# STC12_CH340E.net
KiCad netlist of a schematic drawn in Altium Designer
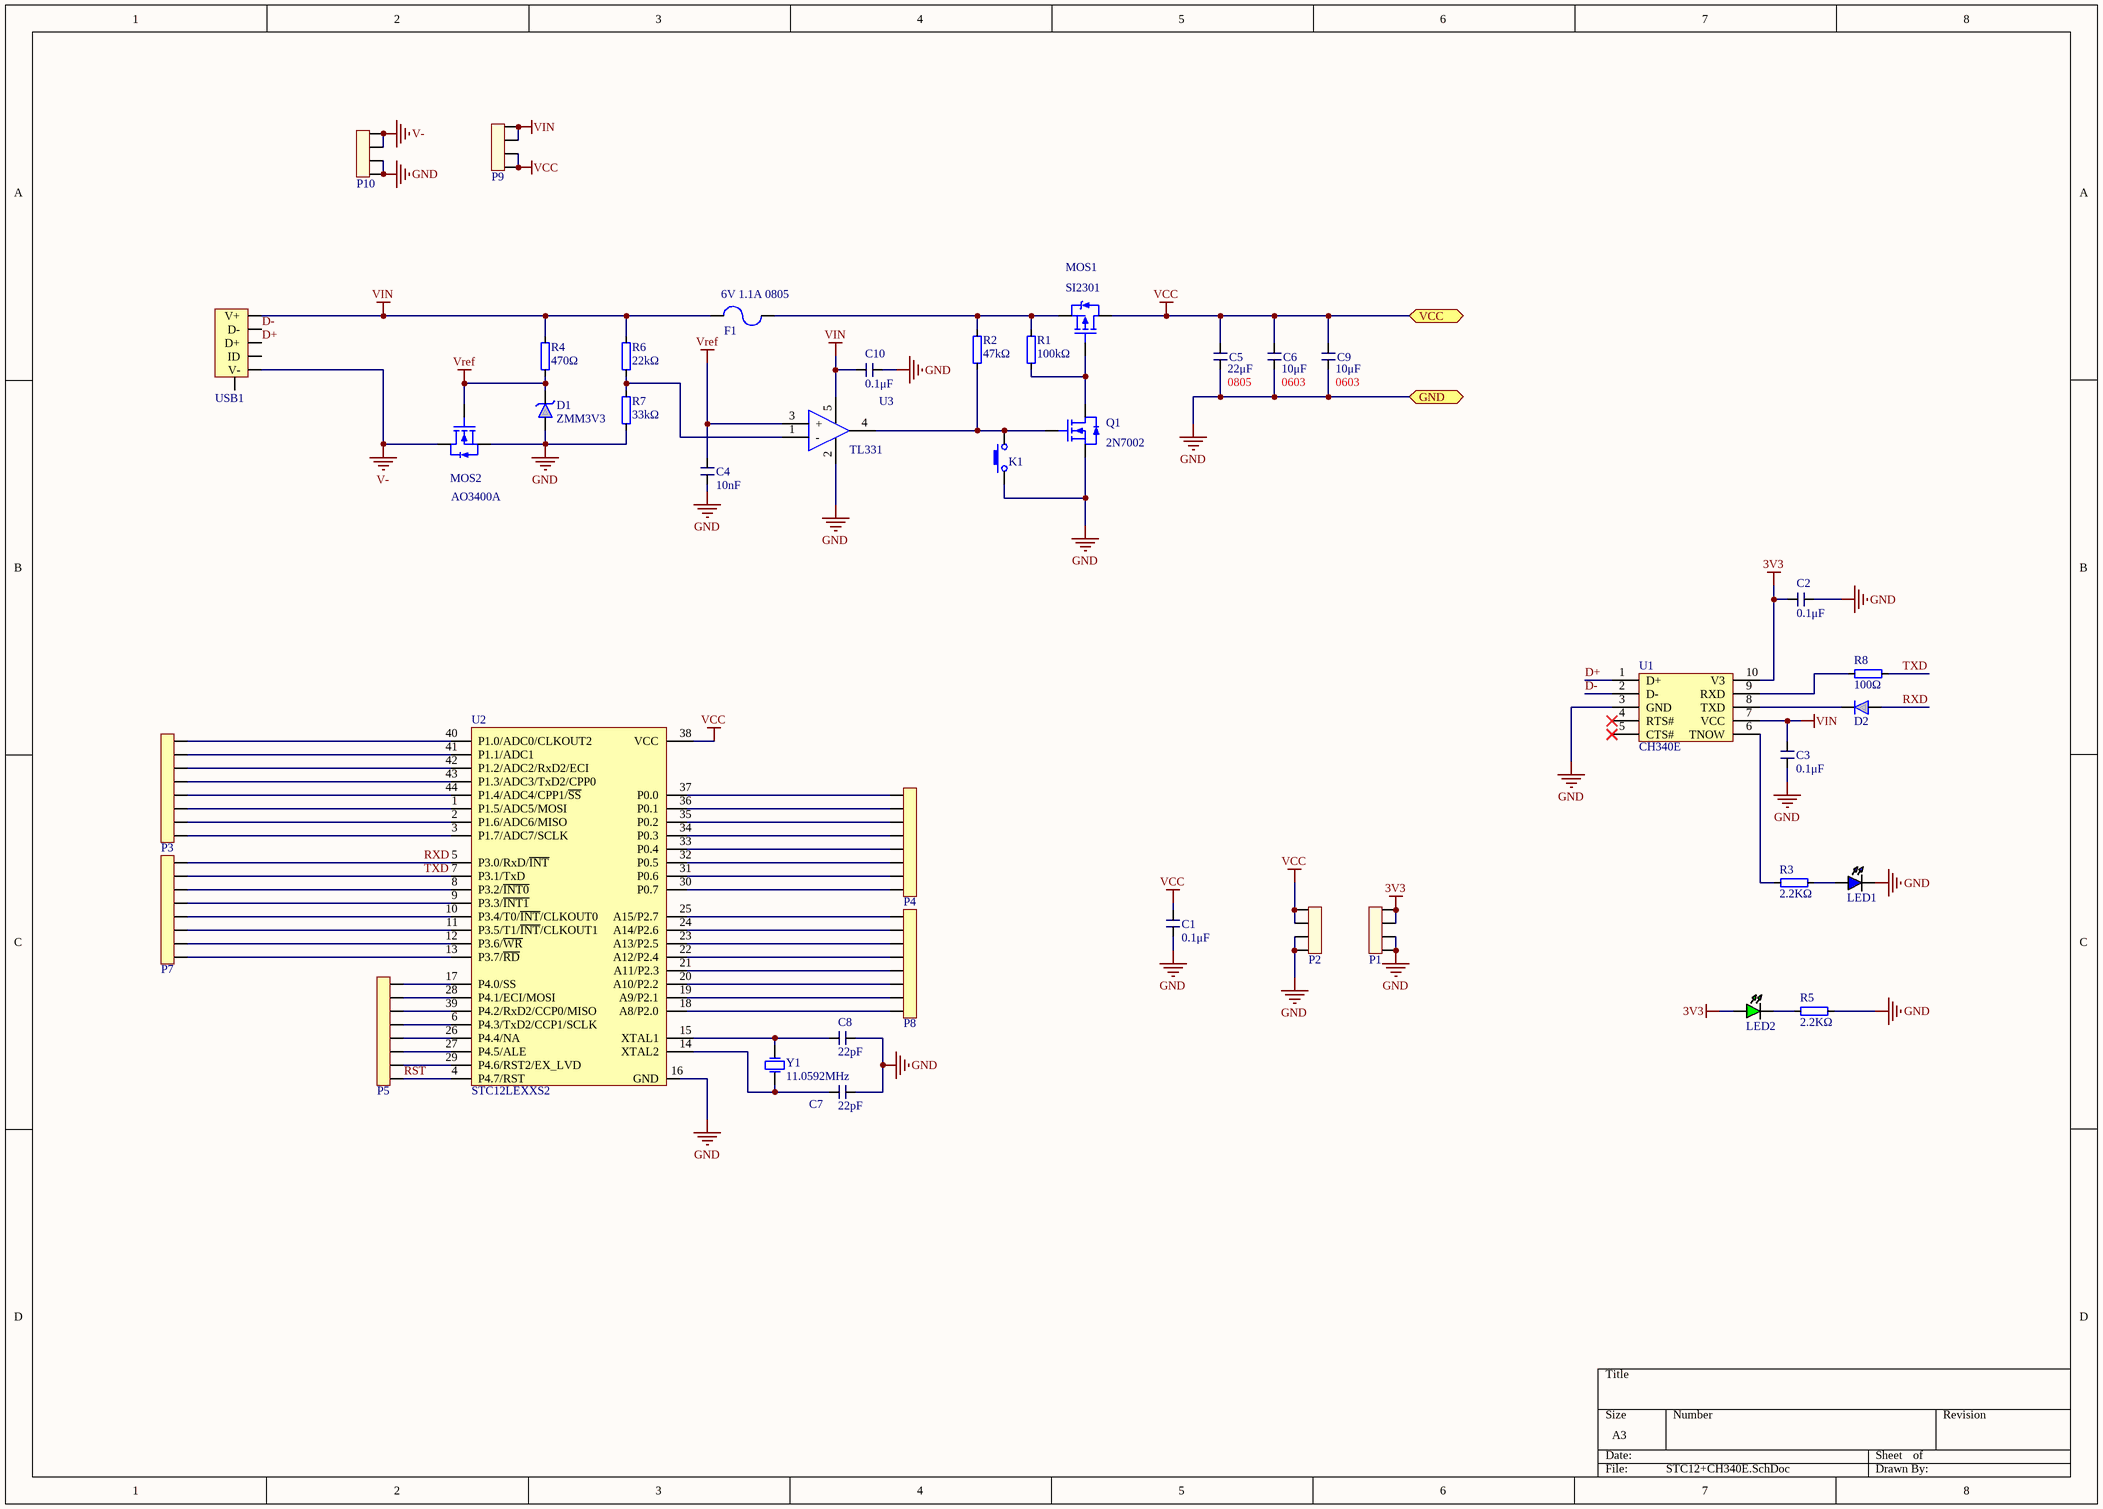
[diagram p0: STC12+CH340E.SchDoc]

(export (version "E")
  (design (tool "Eeschema 10.0.6"))
  (components
    (comp (ref "C1") (value "0.1μF") (footprint "C_0603") (libsource (lib "节能库") (part "C_0603")))
    (comp (ref "C2") (value "0.1μF") (footprint "C_0603") (libsource (lib "节能库") (part "C_0603")))
    (comp (ref "C3") (value "0.1μF") (footprint "C_0603") (libsource (lib "节能库") (part "C_0603")))
    (comp (ref "C4") (value "10nF") (footprint "C_0603") (libsource (lib "节能库") (part "C_0603")))
    (comp (ref "C5") (value "22μF") (footprint "C_0805") (libsource (lib "节能库") (part "C_0805")))
    (comp (ref "C6") (value "10μF") (footprint "C_0603") (libsource (lib "节能库") (part "C_0603")))
    (comp (ref "C7") (value "22pF") (footprint "C_0603") (libsource (lib "节能库") (part "C_0603")))
    (comp (ref "C8") (value "22pF") (footprint "C_0603") (libsource (lib "节能库") (part "C_0603")))
    (comp (ref "C9") (value "10μF") (footprint "C_0603") (libsource (lib "节能库") (part "C_0603")))
    (comp (ref "C10") (value "0.1μF") (footprint "C_0603") (libsource (lib "节能库") (part "C_0603")))
    (comp (ref "D1") (value "ZMM3V3") (footprint "SOD_80") (libsource (lib "节能库") (part "ZMMxxV")))
    (comp (ref "D2") (value "1N4148WS") (footprint "SOD_323") (libsource (lib "节能库") (part "1N4148WS")))
    (comp (ref "F1") (value "6V 1.1A 0805") (footprint "FB_0805") (libsource (lib "节能库") (part "FUSE_0805")))
    (comp (ref "K1")
      (value "TACT SWITCH_2_SMD")
      (footprint "TACT SWITCH_2_SMD")
      (libsource (lib "节能库") (part "TACT SWITCH_2_SMD"))
    )
    (comp (ref "LED1")
      (value "LED_0603-B")
      (footprint "LED_0603-B")
      (libsource (lib "节能库") (part "LED_0603-B"))
    )
    (comp (ref "LED2")
      (value "LED_0603-G")
      (footprint "LED_0603-G")
      (libsource (lib "节能库") (part "LED_0603-G"))
    )
    (comp (ref "MOS1") (value "SI2301") (footprint "SOT_23_3") (libsource (lib "节能库") (part "SI2301")))
    (comp (ref "MOS2") (value "AO3400A") (footprint "SOT_23_3") (libsource (lib "节能库") (part "AO3400A")))
    (comp (ref "P1") (value "PIN4") (footprint "PIN_4") (libsource (lib "节能库") (part "PIN4")))
    (comp (ref "P2") (value "PIN4") (footprint "PIN_4") (libsource (lib "") (part "PIN4_1")))
    (comp (ref "P3") (value "PIN8") (footprint "PIN_8") (libsource (lib "节能库") (part "PIN8")))
    (comp (ref "P4") (value "PIN8") (footprint "PIN_8") (libsource (lib "") (part "PIN8_1")))
    (comp (ref "P5") (value "PIN8") (footprint "PIN_8") (libsource (lib "节能库") (part "PIN8")))
    (comp (ref "P7") (value "PIN8") (footprint "PIN_8") (libsource (lib "节能库") (part "PIN8")))
    (comp (ref "P8") (value "PIN8") (footprint "PIN_8") (libsource (lib "") (part "PIN8_1")))
    (comp (ref "P9") (value "PIN4") (footprint "PIN_4") (libsource (lib "") (part "PIN4_2")))
    (comp (ref "P10") (value "PIN4") (footprint "PIN_4") (libsource (lib "") (part "PIN4_2")))
    (comp (ref "Q1") (value "2N7002") (footprint "SOT_23_3") (libsource (lib "节能库") (part "2N7002")))
    (comp (ref "R1") (value "100kΩ") (footprint "R_0603") (libsource (lib "节能库") (part "R_0603")))
    (comp (ref "R2") (value "47kΩ") (footprint "R_0603") (libsource (lib "节能库") (part "R_0603")))
    (comp (ref "R3") (value "2.2KΩ") (footprint "R_0603") (libsource (lib "节能库") (part "R_0603")))
    (comp (ref "R4") (value "470Ω") (footprint "R_0603") (libsource (lib "节能库") (part "R_0603")))
    (comp (ref "R5") (value "2.2KΩ") (footprint "R_0603") (libsource (lib "节能库") (part "R_0603")))
    (comp (ref "R6") (value "22kΩ") (footprint "R_0603") (libsource (lib "节能库") (part "R_0603")))
    (comp (ref "R7") (value "33kΩ") (footprint "R_0603") (libsource (lib "节能库") (part "R_0603")))
    (comp (ref "R8") (value "100Ω") (footprint "R_0603") (libsource (lib "节能库") (part "R_0603")))
    (comp (ref "U1") (value "CH340E") (footprint "MSOP_10") (libsource (lib "节能库") (part "CH340E")))
    (comp (ref "U2")
      (value "STC12LEXXS2")
      (footprint "LQFP_44")
      (libsource (lib "节能库") (part "STC12LE5AXXS2 - LQPF44"))
    )
    (comp (ref "U3") (value "TL331") (footprint "SOT_23_5") (libsource (lib "节能库") (part "TL331")))
    (comp (ref "USB1")
      (value "MICRO USB B")
      (footprint "MICRO USB B")
      (libsource (lib "节能库") (part "MICRO USB B"))
    )
    (comp (ref "Y1")
      (value "11.0592MHz")
      (footprint "Crystal_HC_49US")
      (libsource (lib "节能库") (part "Crystal_HC_49US"))
    )
  )
  (nets
    (net (code "1") (name "/D+") (class "Default")
      (node (ref "U1") (pin "1") (pinfunction "D+_1") (pintype "passive"))
      (node (ref "USB1") (pin "3") (pinfunction "D+_3") (pintype "passive"))
    )
    (net (code "2") (name "/D-") (class "Default")
      (node (ref "U1") (pin "2") (pinfunction "D-_2") (pintype "passive"))
      (node (ref "USB1") (pin "2") (pinfunction "D-_2") (pintype "passive"))
    )
    (net (code "3") (name "/RST") (class "Default")
      (node (ref "P5") (pin "8") (pinfunction "8_8") (pintype "passive"))
      (node (ref "U2") (pin "4") (pinfunction "P4.7/RST_4") (pintype "passive"))
    )
    (net (code "4") (name "/RXD") (class "Default")
      (node (ref "D2") (pin "1") (pinfunction "A_1") (pintype "passive"))
      (node (ref "P7") (pin "1") (pinfunction "1_1") (pintype "passive"))
      (node (ref "U2") (pin "5") (pinfunction "P3.0/RxD/~{INT}_5") (pintype "passive"))
    )
    (net (code "5") (name "/TXD") (class "Default")
      (node (ref "P7") (pin "2") (pinfunction "2_2") (pintype "passive"))
      (node (ref "R8") (pin "2") (pintype "passive"))
      (node (ref "U2") (pin "7") (pinfunction "P3.1/TxD_7") (pintype "passive"))
    )
    (net (code "6") (name "3V3") (class "Default")
      (node (ref "C2") (pin "2") (pinfunction "2_2") (pintype "passive"))
      (node (ref "LED2") (pin "1") (pinfunction "1_1") (pintype "passive"))
      (node (ref "P1") (pin "3") (pinfunction "3_3") (pintype "passive"))
      (node (ref "P1") (pin "4") (pinfunction "4_4") (pintype "passive"))
      (node (ref "U1") (pin "10") (pinfunction "V3_10") (pintype "passive"))
    )
    (net (code "7") (name "GND") (class "Default")
      (node (ref "C1") (pin "2") (pinfunction "2_2") (pintype "passive"))
      (node (ref "C10") (pin "2") (pinfunction "2_2") (pintype "passive"))
      (node (ref "C2") (pin "1") (pinfunction "1_1") (pintype "passive"))
      (node (ref "C3") (pin "1") (pinfunction "1_1") (pintype "passive"))
      (node (ref "C4") (pin "2") (pinfunction "2_2") (pintype "passive"))
      (node (ref "C5") (pin "2") (pinfunction "2_2") (pintype "passive"))
      (node (ref "C6") (pin "2") (pinfunction "2_2") (pintype "passive"))
      (node (ref "C7") (pin "2") (pinfunction "2_2") (pintype "passive"))
      (node (ref "C8") (pin "2") (pinfunction "2_2") (pintype "passive"))
      (node (ref "C9") (pin "2") (pinfunction "2_2") (pintype "passive"))
      (node (ref "D1") (pin "1") (pinfunction "A_1") (pintype "passive"))
      (node (ref "K1") (pin "1") (pinfunction "1_1") (pintype "passive"))
      (node (ref "LED1") (pin "2") (pinfunction "2_2") (pintype "passive"))
      (node (ref "MOS2") (pin "2") (pinfunction "S_2") (pintype "passive"))
      (node (ref "P1") (pin "1") (pinfunction "1_1") (pintype "passive"))
      (node (ref "P1") (pin "2") (pinfunction "2_2") (pintype "passive"))
      (node (ref "P10") (pin "3") (pinfunction "3_3") (pintype "passive"))
      (node (ref "P10") (pin "4") (pinfunction "4_4") (pintype "passive"))
      (node (ref "P2") (pin "1") (pinfunction "1_1") (pintype "passive"))
      (node (ref "P2") (pin "2") (pinfunction "2_2") (pintype "passive"))
      (node (ref "Q1") (pin "2") (pinfunction "S_2") (pintype "passive"))
      (node (ref "R5") (pin "2") (pintype "passive"))
      (node (ref "R7") (pin "1") (pintype "passive"))
      (node (ref "U1") (pin "3") (pinfunction "GND_3") (pintype "passive"))
      (node (ref "U2") (pin "16") (pinfunction "GND_16") (pintype "passive"))
      (node (ref "U3") (pin "2") (pinfunction "GND_2") (pintype "passive"))
    )
    (net (code "8") (name "Net-(D2-K)") (class "Default")
      (node (ref "D2") (pin "2") (pinfunction "K_2") (pintype "passive"))
      (node (ref "U1") (pin "8") (pinfunction "TXD_8") (pintype "passive"))
    )
    (net (code "9") (name "Net-(LED1-Pad1)") (class "Default")
      (node (ref "LED1") (pin "1") (pinfunction "1_1") (pintype "passive"))
      (node (ref "R3") (pin "2") (pintype "passive"))
    )
    (net (code "10") (name "Net-(LED2-Pad2)") (class "Default")
      (node (ref "LED2") (pin "2") (pinfunction "2_2") (pintype "passive"))
      (node (ref "R5") (pin "1") (pintype "passive"))
    )
    (net (code "11") (name "Net-(MOS1-G)") (class "Default")
      (node (ref "MOS1") (pin "1") (pinfunction "G_1") (pintype "passive"))
      (node (ref "Q1") (pin "3") (pinfunction "D_3") (pintype "passive"))
      (node (ref "R1") (pin "1") (pintype "passive"))
    )
    (net (code "12") (name "Net-(MOS1-S)") (class "Default")
      (node (ref "F1") (pin "2") (pinfunction "2_2") (pintype "passive"))
      (node (ref "MOS1") (pin "2") (pinfunction "S_2") (pintype "passive"))
      (node (ref "R1") (pin "2") (pintype "passive"))
      (node (ref "R2") (pin "2") (pintype "passive"))
    )
    (net (code "13") (name "Net-(Q1-G)") (class "Default")
      (node (ref "K1") (pin "2") (pinfunction "2_2") (pintype "passive"))
      (node (ref "Q1") (pin "1") (pinfunction "G_1") (pintype "passive"))
      (node (ref "R2") (pin "1") (pintype "passive"))
      (node (ref "U3") (pin "4") (pinfunction "OUT_4") (pintype "passive"))
    )
    (net (code "14") (name "Net-(U1-RXD)") (class "Default")
      (node (ref "R8") (pin "1") (pintype "passive"))
      (node (ref "U1") (pin "9") (pinfunction "RXD_9") (pintype "passive"))
    )
    (net (code "15") (name "Net-(U1-TNOW)") (class "Default")
      (node (ref "R3") (pin "1") (pintype "passive"))
      (node (ref "U1") (pin "6") (pinfunction "TNOW_6") (pintype "passive"))
    )
    (net (code "16") (name "Net-(U2-A8{slash}P2.0)") (class "Default")
      (node (ref "P8") (pin "1") (pinfunction "1_1") (pintype "passive"))
      (node (ref "U2") (pin "18") (pinfunction "A8/P2.0_18") (pintype "passive"))
    )
    (net (code "17") (name "Net-(U2-A9{slash}P2.1)") (class "Default")
      (node (ref "P8") (pin "2") (pinfunction "2_2") (pintype "passive"))
      (node (ref "U2") (pin "19") (pinfunction "A9/P2.1_19") (pintype "passive"))
    )
    (net (code "18") (name "Net-(U2-A10{slash}P2.2)") (class "Default")
      (node (ref "P8") (pin "3") (pinfunction "3_3") (pintype "passive"))
      (node (ref "U2") (pin "20") (pinfunction "A10/P2.2_20") (pintype "passive"))
    )
    (net (code "19") (name "Net-(U2-A11{slash}P2.3)") (class "Default")
      (node (ref "P8") (pin "4") (pinfunction "4_4") (pintype "passive"))
      (node (ref "U2") (pin "21") (pinfunction "A11/P2.3_21") (pintype "passive"))
    )
    (net (code "20") (name "Net-(U2-A12{slash}P2.4)") (class "Default")
      (node (ref "P8") (pin "5") (pinfunction "5_5") (pintype "passive"))
      (node (ref "U2") (pin "22") (pinfunction "A12/P2.4_22") (pintype "passive"))
    )
    (net (code "21") (name "Net-(U2-A13{slash}P2.5)") (class "Default")
      (node (ref "P8") (pin "6") (pinfunction "6_6") (pintype "passive"))
      (node (ref "U2") (pin "23") (pinfunction "A13/P2.5_23") (pintype "passive"))
    )
    (net (code "22") (name "Net-(U2-A14{slash}P2.6)") (class "Default")
      (node (ref "P8") (pin "7") (pinfunction "7_7") (pintype "passive"))
      (node (ref "U2") (pin "24") (pinfunction "A14/P2.6_24") (pintype "passive"))
    )
    (net (code "23") (name "Net-(U2-A15{slash}P2.7)") (class "Default")
      (node (ref "P8") (pin "8") (pinfunction "8_8") (pintype "passive"))
      (node (ref "U2") (pin "25") (pinfunction "A15/P2.7_25") (pintype "passive"))
    )
    (net (code "24") (name "Net-(U2-P0.0)") (class "Default")
      (node (ref "P4") (pin "8") (pinfunction "8_8") (pintype "passive"))
      (node (ref "U2") (pin "37") (pinfunction "P0.0_37") (pintype "passive"))
    )
    (net (code "25") (name "Net-(U2-P0.1)") (class "Default")
      (node (ref "P4") (pin "7") (pinfunction "7_7") (pintype "passive"))
      (node (ref "U2") (pin "36") (pinfunction "P0.1_36") (pintype "passive"))
    )
    (net (code "26") (name "Net-(U2-P0.2)") (class "Default")
      (node (ref "P4") (pin "6") (pinfunction "6_6") (pintype "passive"))
      (node (ref "U2") (pin "35") (pinfunction "P0.2_35") (pintype "passive"))
    )
    (net (code "27") (name "Net-(U2-P0.3)") (class "Default")
      (node (ref "P4") (pin "5") (pinfunction "5_5") (pintype "passive"))
      (node (ref "U2") (pin "34") (pinfunction "P0.3_34") (pintype "passive"))
    )
    (net (code "28") (name "Net-(U2-P0.4)") (class "Default")
      (node (ref "P4") (pin "4") (pinfunction "4_4") (pintype "passive"))
      (node (ref "U2") (pin "33") (pinfunction "P0.4_33") (pintype "passive"))
    )
    (net (code "29") (name "Net-(U2-P0.5)") (class "Default")
      (node (ref "P4") (pin "3") (pinfunction "3_3") (pintype "passive"))
      (node (ref "U2") (pin "32") (pinfunction "P0.5_32") (pintype "passive"))
    )
    (net (code "30") (name "Net-(U2-P0.6)") (class "Default")
      (node (ref "P4") (pin "2") (pinfunction "2_2") (pintype "passive"))
      (node (ref "U2") (pin "31") (pinfunction "P0.6_31") (pintype "passive"))
    )
    (net (code "31") (name "Net-(U2-P0.7)") (class "Default")
      (node (ref "P4") (pin "1") (pinfunction "1_1") (pintype "passive"))
      (node (ref "U2") (pin "30") (pinfunction "P0.7_30") (pintype "passive"))
    )
    (net (code "32") (name "Net-(U2-P1.0{slash}ADC0{slash}CLKOUT2)") (class "Default")
      (node (ref "P3") (pin "1") (pinfunction "1_1") (pintype "passive"))
      (node (ref "U2") (pin "40") (pinfunction "P1.0/ADC0/CLKOUT2_40") (pintype "passive"))
    )
    (net (code "33") (name "Net-(U2-P1.1{slash}ADC1)") (class "Default")
      (node (ref "P3") (pin "2") (pinfunction "2_2") (pintype "passive"))
      (node (ref "U2") (pin "41") (pinfunction "P1.1/ADC1_41") (pintype "passive"))
    )
    (net (code "34") (name "Net-(U2-P1.2{slash}ADC2{slash}RxD2{slash}ECI)") (class "Default")
      (node (ref "P3") (pin "3") (pinfunction "3_3") (pintype "passive"))
      (node (ref "U2") (pin "42") (pinfunction "P1.2/ADC2/RxD2/ECI_42") (pintype "passive"))
    )
    (net (code "35") (name "Net-(U2-P1.3{slash}ADC3{slash}TxD2{slash}CPP0)") (class "Default")
      (node (ref "P3") (pin "4") (pinfunction "4_4") (pintype "passive"))
      (node (ref "U2") (pin "43") (pinfunction "P1.3/ADC3/TxD2/CPP0_43") (pintype "passive"))
    )
    (net (code "36") (name "Net-(U2-P1.4{slash}ADC4{slash}CPP1{slash}~{SS})") (class "Default")
      (node (ref "P3") (pin "5") (pinfunction "5_5") (pintype "passive"))
      (node (ref "U2") (pin "44") (pinfunction "P1.4/ADC4/CPP1/~{SS}_44") (pintype "passive"))
    )
    (net (code "37") (name "Net-(U2-P1.5{slash}ADC5{slash}MOSI)") (class "Default")
      (node (ref "P3") (pin "6") (pinfunction "6_6") (pintype "passive"))
      (node (ref "U2") (pin "1") (pinfunction "P1.5/ADC5/MOSI_1") (pintype "passive"))
    )
    (net (code "38") (name "Net-(U2-P1.6{slash}ADC6{slash}MISO)") (class "Default")
      (node (ref "P3") (pin "7") (pinfunction "7_7") (pintype "passive"))
      (node (ref "U2") (pin "2") (pinfunction "P1.6/ADC6/MISO_2") (pintype "passive"))
    )
    (net (code "39") (name "Net-(U2-P1.7{slash}ADC7{slash}SCLK)") (class "Default")
      (node (ref "P3") (pin "8") (pinfunction "8_8") (pintype "passive"))
      (node (ref "U2") (pin "3") (pinfunction "P1.7/ADC7/SCLK_3") (pintype "passive"))
    )
    (net (code "40") (name "Net-(U2-P3.2{slash}~{INT0})") (class "Default")
      (node (ref "P7") (pin "3") (pinfunction "3_3") (pintype "passive"))
      (node (ref "U2") (pin "8") (pinfunction "P3.2/~{INT0}_8") (pintype "passive"))
    )
    (net (code "41") (name "Net-(U2-P3.3{slash}~{INT1})") (class "Default")
      (node (ref "P7") (pin "4") (pinfunction "4_4") (pintype "passive"))
      (node (ref "U2") (pin "9") (pinfunction "P3.3/~{INT1}_9") (pintype "passive"))
    )
    (net (code "42") (name "Net-(U2-P3.4{slash}T0{slash}~{INT}{slash}CLKOUT0)") (class "Default")
      (node (ref "P7") (pin "5") (pinfunction "5_5") (pintype "passive"))
      (node (ref "U2") (pin "10") (pinfunction "P3.4/T0/~{INT}/CLKOUT0_10") (pintype "passive"))
    )
    (net (code "43") (name "Net-(U2-P3.5{slash}T1{slash}~{INT}{slash}CLKOUT1)") (class "Default")
      (node (ref "P7") (pin "6") (pinfunction "6_6") (pintype "passive"))
      (node (ref "U2") (pin "11") (pinfunction "P3.5/T1/~{INT}/CLKOUT1_11") (pintype "passive"))
    )
    (net (code "44") (name "Net-(U2-P3.6{slash}~{WR})") (class "Default")
      (node (ref "P7") (pin "7") (pinfunction "7_7") (pintype "passive"))
      (node (ref "U2") (pin "12") (pinfunction "P3.6/~{WR}_12") (pintype "passive"))
    )
    (net (code "45") (name "Net-(U2-P3.7{slash}~{RD})") (class "Default")
      (node (ref "P7") (pin "8") (pinfunction "8_8") (pintype "passive"))
      (node (ref "U2") (pin "13") (pinfunction "P3.7/~{RD}_13") (pintype "passive"))
    )
    (net (code "46") (name "Net-(U2-P4.0{slash}SS)") (class "Default")
      (node (ref "P5") (pin "1") (pinfunction "1_1") (pintype "passive"))
      (node (ref "U2") (pin "17") (pinfunction "P4.0/SS_17") (pintype "passive"))
    )
    (net (code "47") (name "Net-(U2-P4.1{slash}ECI{slash}MOSI)") (class "Default")
      (node (ref "P5") (pin "2") (pinfunction "2_2") (pintype "passive"))
      (node (ref "U2") (pin "28") (pinfunction "P4.1/ECI/MOSI_28") (pintype "passive"))
    )
    (net (code "48") (name "Net-(U2-P4.2{slash}RxD2{slash}CCP0{slash}MISO)") (class "Default")
      (node (ref "P5") (pin "3") (pinfunction "3_3") (pintype "passive"))
      (node (ref "U2") (pin "39") (pinfunction "P4.2/RxD2/CCP0/MISO_39") (pintype "passive"))
    )
    (net (code "49") (name "Net-(U2-P4.3{slash}TxD2{slash}CCP1{slash}SCLK)") (class "Default")
      (node (ref "P5") (pin "4") (pinfunction "4_4") (pintype "passive"))
      (node (ref "U2") (pin "6") (pinfunction "P4.3/TxD2/CCP1/SCLK_6") (pintype "passive"))
    )
    (net (code "50") (name "Net-(U2-P4.4{slash}NA)") (class "Default")
      (node (ref "P5") (pin "5") (pinfunction "5_5") (pintype "passive"))
      (node (ref "U2") (pin "26") (pinfunction "P4.4/NA_26") (pintype "passive"))
    )
    (net (code "51") (name "Net-(U2-P4.5{slash}ALE)") (class "Default")
      (node (ref "P5") (pin "6") (pinfunction "6_6") (pintype "passive"))
      (node (ref "U2") (pin "27") (pinfunction "P4.5/ALE_27") (pintype "passive"))
    )
    (net (code "52") (name "Net-(U2-P4.6{slash}RST2{slash}EX_LVD)") (class "Default")
      (node (ref "P5") (pin "7") (pinfunction "7_7") (pintype "passive"))
      (node (ref "U2") (pin "29") (pinfunction "P4.6/RST2/EX_LVD_29") (pintype "passive"))
    )
    (net (code "53") (name "Net-(U2-XTAL1)") (class "Default")
      (node (ref "C8") (pin "1") (pinfunction "1_1") (pintype "passive"))
      (node (ref "U2") (pin "15") (pinfunction "XTAL1_15") (pintype "passive"))
      (node (ref "Y1") (pin "2") (pinfunction "OSC2_2") (pintype "passive"))
    )
    (net (code "54") (name "Net-(U2-XTAL2)") (class "Default")
      (node (ref "C7") (pin "1") (pinfunction "1_1") (pintype "passive"))
      (node (ref "U2") (pin "14") (pinfunction "XTAL2_14") (pintype "passive"))
      (node (ref "Y1") (pin "1") (pinfunction "OSC1_1") (pintype "passive"))
    )
    (net (code "55") (name "Net-(U3--)") (class "Default")
      (node (ref "R6") (pin "1") (pintype "passive"))
      (node (ref "R7") (pin "2") (pintype "passive"))
      (node (ref "U3") (pin "1") (pinfunction "-_1") (pintype "passive"))
    )
    (net (code "56") (name "V-") (class "Default")
      (node (ref "MOS2") (pin "3") (pinfunction "D_3") (pintype "passive"))
      (node (ref "P10") (pin "1") (pinfunction "1_1") (pintype "passive"))
      (node (ref "P10") (pin "2") (pinfunction "2_2") (pintype "passive"))
      (node (ref "USB1") (pin "5") (pinfunction "V-_5") (pintype "passive"))
    )
    (net (code "57") (name "VCC") (class "Default")
      (node (ref "C1") (pin "1") (pinfunction "1_1") (pintype "passive"))
      (node (ref "C5") (pin "1") (pinfunction "1_1") (pintype "passive"))
      (node (ref "C6") (pin "1") (pinfunction "1_1") (pintype "passive"))
      (node (ref "C9") (pin "1") (pinfunction "1_1") (pintype "passive"))
      (node (ref "MOS1") (pin "3") (pinfunction "D_3") (pintype "passive"))
      (node (ref "P2") (pin "3") (pinfunction "3_3") (pintype "passive"))
      (node (ref "P2") (pin "4") (pinfunction "4_4") (pintype "passive"))
      (node (ref "P9") (pin "3") (pinfunction "3_3") (pintype "passive"))
      (node (ref "P9") (pin "4") (pinfunction "4_4") (pintype "passive"))
      (node (ref "U2") (pin "38") (pinfunction "VCC_38") (pintype "passive"))
    )
    (net (code "58") (name "VIN") (class "Default")
      (node (ref "C10") (pin "1") (pinfunction "1_1") (pintype "passive"))
      (node (ref "C3") (pin "2") (pinfunction "2_2") (pintype "passive"))
      (node (ref "F1") (pin "1") (pinfunction "1_1") (pintype "passive"))
      (node (ref "P9") (pin "1") (pinfunction "1_1") (pintype "passive"))
      (node (ref "P9") (pin "2") (pinfunction "2_2") (pintype "passive"))
      (node (ref "R4") (pin "2") (pintype "passive"))
      (node (ref "R6") (pin "2") (pintype "passive"))
      (node (ref "U1") (pin "7") (pinfunction "VCC_7") (pintype "passive"))
      (node (ref "U3") (pin "5") (pinfunction "VCC_5") (pintype "passive"))
      (node (ref "USB1") (pin "1") (pinfunction "V+_1") (pintype "passive"))
    )
    (net (code "59") (name "Vref") (class "Default")
      (node (ref "C4") (pin "1") (pinfunction "1_1") (pintype "passive"))
      (node (ref "D1") (pin "2") (pinfunction "K_2") (pintype "passive"))
      (node (ref "MOS2") (pin "1") (pinfunction "G_1") (pintype "passive"))
      (node (ref "R4") (pin "1") (pintype "passive"))
      (node (ref "U3") (pin "3") (pinfunction "+_3") (pintype "passive"))
    )
    (net (code "60") (name "unconnected-(U1-CTS#-Pad5)") (class "Default")
      (node (ref "U1") (pin "5") (pinfunction "CTS#_5") (pintype "passive+no_connect"))
    )
    (net (code "61") (name "unconnected-(U1-RTS#-Pad4)") (class "Default")
      (node (ref "U1") (pin "4") (pinfunction "RTS#_4") (pintype "passive+no_connect"))
    )
    (net (code "62") (name "unconnected-(USB1-GND-Pad0)") (class "Default")
      (node (ref "USB1") (pin "0") (pinfunction "GND_0") (pintype "passive"))
    )
    (net (code "63") (name "unconnected-(USB1-ID-Pad4)") (class "Default")
      (node (ref "USB1") (pin "4") (pinfunction "ID_4") (pintype "passive"))
    )
  )
)
